# GPS.net
KiCad netlist of a schematic drawn in Altium Designer
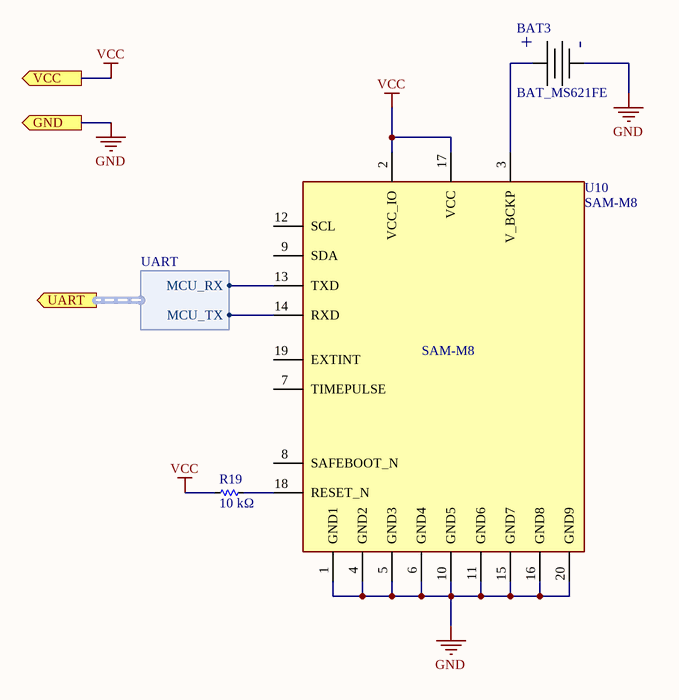
[diagram p0: GPS.SchDoc]

(export (version "E")
  (design (tool "Eeschema 10.0.6"))
  (components
    (comp (ref "BAT3")
      (value "BAT_MS621FE")
      (footprint "BATT_COINCELL_RECHARGEABLE")
      (description "MS621FE RECHARGEABLE COIN CELL BACKUP")
      (fields
        (field (name "MANUFACTURER") "Seiko Instruments")
        (field (name "MANUFACTURER PART NUMBER") "MS621FE-FL11E")
      )
      (libsource (lib "Stanford Student Space Initiative") (part "BAT_MS621FE"))
    )
    (comp (ref "R19")
      (value "311-10.0KHRCT-ND")
      (footprint "R0603")
      (description "RES SMD 10K OHM 1% 1/10W 0603")
      (fields
        (field (name "RESISTANCE") "10 kΩ")
        (field (name "MANUFACTURER PART NUMBER") "RC0603FR-0710KL")
        (field (name "MANUFACTURER") "Yageo")
      )
      (libsource (lib "Stanford Student Space Initiative") (part "__template_resistor"))
    )
    (comp (ref "U10")
      (value "SAM-M8")
      (footprint "SAM-M8")
      (description "ublox SAM GNSS antenna module")
      (fields (field (name "MANUFACTURER") "u-blox"))
      (libsource (lib "ubloxLib") (part "SAM-M8"))
    )
  )
  (nets
    (net (code "2") (name "/MCU_RX") (class "Default")
      (node (ref "U10") (pin "13") (pinfunction "TXD_13") (pintype "passive"))
    )
    (net (code "3") (name "/MCU_TX") (class "Default")
      (node (ref "U10") (pin "14") (pinfunction "RXD_14") (pintype "passive"))
    )
    (net (code "5") (name "GND") (class "Default")
      (node (ref "BAT3") (pin "-") (pintype "passive"))
      (node (ref "U10") (pin "1") (pinfunction "GND1_1") (pintype "passive"))
      (node (ref "U10") (pin "10") (pinfunction "GND5_10") (pintype "passive"))
      (node (ref "U10") (pin "11") (pinfunction "GND6_11") (pintype "passive"))
      (node (ref "U10") (pin "15") (pinfunction "GND7_15") (pintype "passive"))
      (node (ref "U10") (pin "16") (pinfunction "GND8_16") (pintype "passive"))
      (node (ref "U10") (pin "20") (pinfunction "GND9_20") (pintype "passive"))
      (node (ref "U10") (pin "4") (pinfunction "GND2_4") (pintype "passive"))
      (node (ref "U10") (pin "5") (pinfunction "GND3_5") (pintype "passive"))
      (node (ref "U10") (pin "6") (pinfunction "GND4_6") (pintype "passive"))
    )
    (net (code "6") (name "Net-(U10-RESET_N)") (class "Default")
      (node (ref "R19") (pin "2") (pintype "passive"))
      (node (ref "U10") (pin "18") (pinfunction "RESET_N_18") (pintype "passive"))
    )
    (net (code "7") (name "Net-(U10-V_BCKP)") (class "Default")
      (node (ref "BAT3") (pin "+") (pintype "passive"))
      (node (ref "U10") (pin "3") (pinfunction "V_BCKP_3") (pintype "passive"))
    )
    (net (code "8") (name "VCC") (class "Default")
      (node (ref "R19") (pin "1") (pintype "passive"))
      (node (ref "U10") (pin "17") (pinfunction "VCC_17") (pintype "passive"))
      (node (ref "U10") (pin "2") (pinfunction "VCC_IO_2") (pintype "passive"))
    )
    (net (code "9") (name "unconnected-(U10-EXTINT-Pad19)") (class "Default")
      (node (ref "U10") (pin "19") (pinfunction "EXTINT_19") (pintype "passive"))
    )
    (net (code "10") (name "unconnected-(U10-SAFEBOOT_N-Pad8)") (class "Default")
      (node (ref "U10") (pin "8") (pinfunction "SAFEBOOT_N_8") (pintype "passive"))
    )
    (net (code "11") (name "unconnected-(U10-SCL-Pad12)") (class "Default")
      (node (ref "U10") (pin "12") (pinfunction "SCL_12") (pintype "passive"))
    )
    (net (code "12") (name "unconnected-(U10-SDA-Pad9)") (class "Default")
      (node (ref "U10") (pin "9") (pinfunction "SDA_9") (pintype "passive"))
    )
    (net (code "13") (name "unconnected-(U10-TIMEPULSE-Pad7)") (class "Default")
      (node (ref "U10") (pin "7") (pinfunction "TIMEPULSE_7") (pintype "passive"))
    )
  )
)
